# 02-Power.net
KiCad netlist of a schematic drawn in Altium Designer
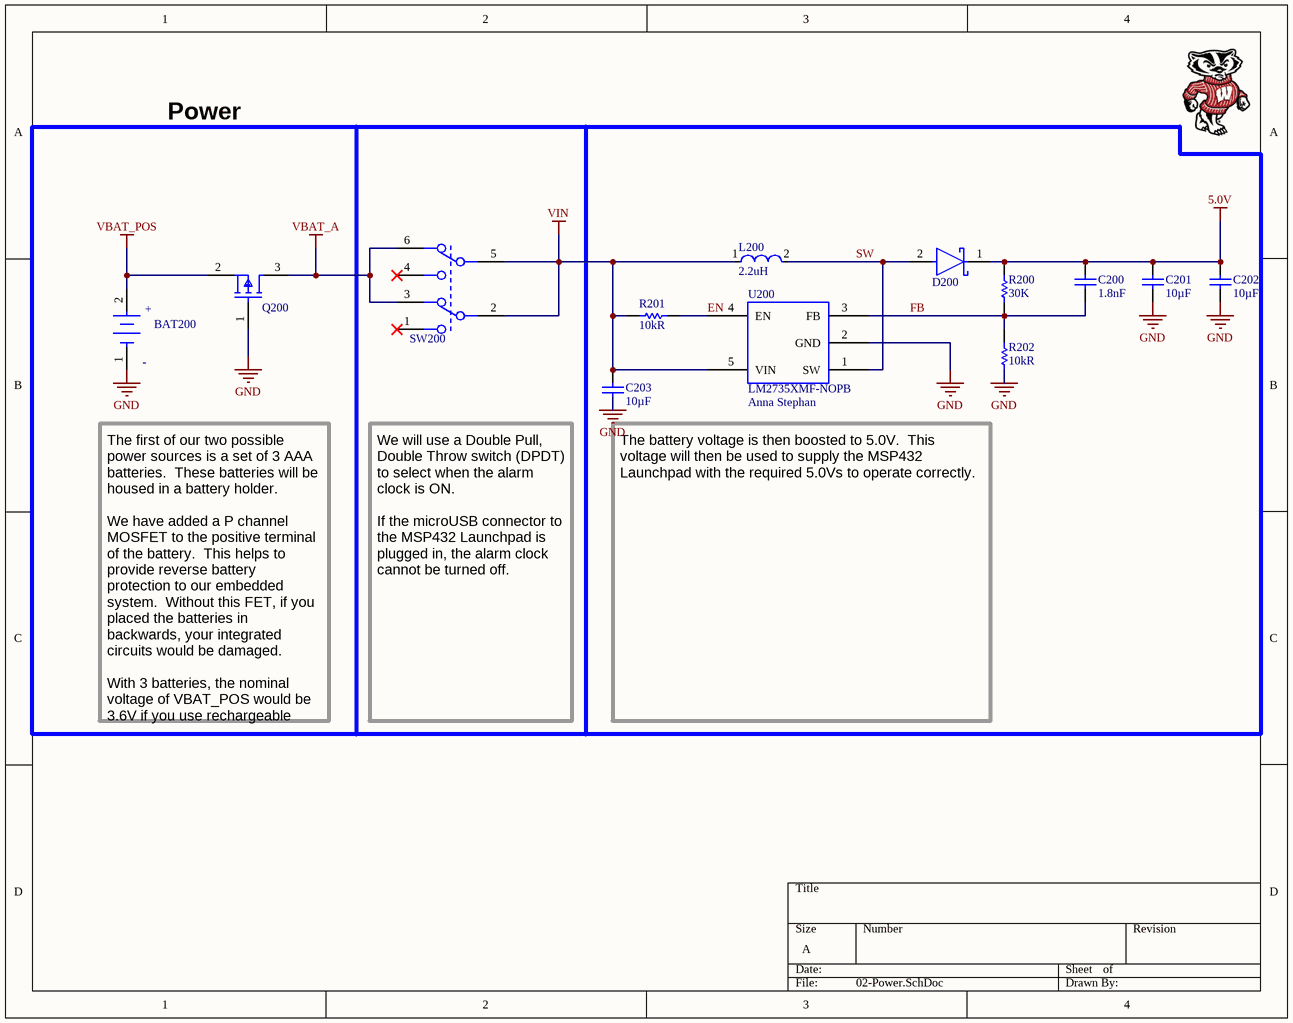
[diagram p0: 02-Power.SchDoc]

(export (version "E")
  (design (tool "Eeschema 10.0.6"))
  (components
    (comp (ref "BAT200")
      (value "UNK_Keystone_2479_eec")
      (footprint "Keystone_2479_0")
      (description "BATTERY HOLDER AAA 3 CELL PC PIN")
      (fields (field (name "PART NUMBER") "2479") (field (name "MANUFACTURER") "Keystone"))
      (libsource (lib "Battery") (part "UNK_Keystone_2479_eec"))
    )
    (comp (ref "C200")
      (value "CAP_0805_N_001_80")
      (footprint "CAP_0805")
      (fields
        (field (name "TOLERANCE") "5%")
        (field (name "VOLTAGE") "50V")
        (field (name "CAPACITANCE") "1.8nF")
      )
      (libsource (lib "ece315") (part "CAP_0805_N_001_80"))
    )
    (comp (ref "C201")
      (value "10µF")
      (footprint "CAP_0805")
      (description "CAP CER 10UF 10V X5R 0805")
      (fields
        (field (name "MANUFACTURER") "Samsung Electro-Mechanics America, Inc.")
        (field (name "MANUFACTURER PART NUMBER") "CL21A106KPCLQNC")
      )
      (libsource (lib "Cap_Ceramic") (part "CAP_0805_U_010_00"))
    )
    (comp (ref "C202")
      (value "10µF")
      (footprint "CAP_0805")
      (description "CAP CER 10UF 10V X5R 0805")
      (fields
        (field (name "MANUFACTURER") "Samsung Electro-Mechanics America, Inc.")
        (field (name "MANUFACTURER PART NUMBER") "CL21A106KPCLQNC")
      )
      (libsource (lib "Cap_Ceramic") (part "CAP_0805_U_010_00"))
    )
    (comp (ref "C203")
      (value "10µF")
      (footprint "CAP_0805")
      (description "CAP CER 10UF 10V X5R 0805")
      (fields
        (field (name "MANUFACTURER") "Samsung Electro-Mechanics America, Inc.")
        (field (name "MANUFACTURER PART NUMBER") "CL21A106KPCLQNC")
      )
      (libsource (lib "Cap_Ceramic") (part "CAP_0805_U_010_00"))
    )
    (comp (ref "D200")
      (value "SM5817PL-TP")
      (footprint "On_Semiconductor_425-04_IPC_A")
      (description "DIODE SCHOTTKY 20V 1A SOD123FL")
      (libsource (lib "ece315") (part "SM5817PL-TP"))
    )
    (comp (ref "L200")
      (value "NRS4018T2R2MDGJ")
      (footprint "IND_TAIYO_NRS4018_TAY")
      (description "Inductor Power Shielded Wirewound 2.2uH 20% 100KHz Ferrite 2.2A 0.0504Ohm DCR 1515 T/R")
      (fields (field (name "TOLERANCE") "20%") (field (name "INDUCTANCE") "2.2uH"))
      (libsource (lib "ece315") (part "NRS4018T2R2MDGJ"))
    )
    (comp (ref "Q200")
      (value "SSM3J328R,LF")
      (footprint "SOT-23_M")
      (description "MOSFET P-CH 20V 6A SOT23F")
      (libsource (lib "Transistors") (part "SSM3J328R,LF"))
    )
    (comp (ref "R200")
      (value "30K")
      (footprint "RES_0805")
      (description "Res Thick Film 0805 30K Ohm 1% 0.125W(1/8W) ±100ppm/°C Pad SMD Automotive T/R")
      (fields (field (name "TOLERANCE") "1%") (field (name "RESISTANCE") "30K"))
      (libsource (lib "ece315") (part "RES_0805_K_030.00"))
    )
    (comp (ref "R201")
      (value "RES_0805_K_010.00")
      (footprint "RES_0805")
      (description "RES SMD 10K OHM 1% 1/8W 0805")
      (fields (field (name "TOLERANCE") "1%") (field (name "RESISTANCE") "10kR"))
      (libsource (lib "ece315") (part "RES_0805_K_010.00"))
    )
    (comp (ref "R202")
      (value "RES_0805_K_010.00")
      (footprint "RES_0805")
      (description "RES SMD 10K OHM 1% 1/8W 0805")
      (fields (field (name "TOLERANCE") "1%") (field (name "RESISTANCE") "10kR"))
      (libsource (lib "ece315") (part "RES_0805_K_010.00"))
    )
    (comp (ref "SW200")
      (value "JS202011SCQN")
      (footprint "C&K_Components_0_MFG")
      (description "C & K COMPONENTS - JS202011SCQN - SWITCH, DPDT, 0.6A, 6VDC, SMD")
      (libsource (lib "Switches") (part "JS202011SCQN"))
    )
    (comp (ref "U200")
      (value "LM2735XMF-NOPB")
      (footprint "LM2735-SOT23-S")
      (description "IC REG MULT CONFG ADJ 2.1A SOT23")
      (fields (field (name "DRAWN_BY") "Anna Stephan"))
      (libsource (lib "ece315") (part "LM2735XMF-NOPB"))
    )
  )
  (nets
    (net (code "1") (name "/EN") (class "Default")
      (node (ref "R201") (pin "1") (pinfunction "1_1") (pintype "passive"))
      (node (ref "U200") (pin "4") (pinfunction "EN_4") (pintype "passive"))
    )
    (net (code "2") (name "/FB") (class "Default")
      (node (ref "C200") (pin "1") (pinfunction "1_1") (pintype "passive"))
      (node (ref "R200") (pin "1") (pinfunction "1_1") (pintype "passive"))
      (node (ref "R202") (pin "2") (pinfunction "2_2") (pintype "passive"))
      (node (ref "U200") (pin "3") (pinfunction "FB_3") (pintype "passive"))
    )
    (net (code "3") (name "/SW") (class "Default")
      (node (ref "D200") (pin "2") (pinfunction "A_2") (pintype "passive"))
      (node (ref "L200") (pin "2") (pinfunction "2_2") (pintype "passive"))
      (node (ref "U200") (pin "1") (pinfunction "SW_1") (pintype "passive"))
    )
    (net (code "4") (name "5.0V") (class "Default")
      (node (ref "C200") (pin "2") (pinfunction "2_2") (pintype "passive"))
      (node (ref "C201") (pin "2") (pinfunction "2_2") (pintype "passive"))
      (node (ref "C202") (pin "2") (pinfunction "2_2") (pintype "passive"))
      (node (ref "D200") (pin "1") (pinfunction "C_1") (pintype "passive"))
      (node (ref "R200") (pin "2") (pinfunction "2_2") (pintype "passive"))
    )
    (net (code "5") (name "GND") (class "Default")
      (node (ref "BAT200") (pin "1") (pinfunction "C_1") (pintype "passive"))
      (node (ref "C201") (pin "1") (pinfunction "1_1") (pintype "passive"))
      (node (ref "C202") (pin "1") (pinfunction "1_1") (pintype "passive"))
      (node (ref "C203") (pin "1") (pinfunction "1_1") (pintype "passive"))
      (node (ref "Q200") (pin "1") (pinfunction "Gate_1") (pintype "passive"))
      (node (ref "R202") (pin "1") (pinfunction "1_1") (pintype "passive"))
      (node (ref "U200") (pin "2") (pinfunction "GND_2") (pintype "passive"))
    )
    (net (code "6") (name "VBAT_A") (class "Default")
      (node (ref "Q200") (pin "3") (pinfunction "Drain_3") (pintype "passive"))
      (node (ref "SW200") (pin "3") (pinfunction "3_3") (pintype "passive"))
      (node (ref "SW200") (pin "6") (pinfunction "6_6") (pintype "passive"))
    )
    (net (code "7") (name "VBAT_POS") (class "Default")
      (node (ref "BAT200") (pin "2") (pinfunction "A_2") (pintype "passive"))
      (node (ref "Q200") (pin "2") (pinfunction "Source_2") (pintype "passive"))
    )
    (net (code "8") (name "VIN") (class "Default")
      (node (ref "C203") (pin "2") (pinfunction "2_2") (pintype "passive"))
      (node (ref "L200") (pin "1") (pinfunction "1_1") (pintype "passive"))
      (node (ref "R201") (pin "2") (pinfunction "2_2") (pintype "passive"))
      (node (ref "SW200") (pin "2") (pinfunction "2_2") (pintype "passive"))
      (node (ref "SW200") (pin "5") (pinfunction "5_5") (pintype "passive"))
      (node (ref "U200") (pin "5") (pinfunction "VIN_5") (pintype "passive"))
    )
    (net (code "9") (name "unconnected-(SW200-Pad1)") (class "Default")
      (node (ref "SW200") (pin "1") (pinfunction "1_1") (pintype "passive+no_connect"))
    )
    (net (code "10") (name "unconnected-(SW200-Pad4)") (class "Default")
      (node (ref "SW200") (pin "4") (pinfunction "4_4") (pintype "passive+no_connect"))
    )
  )
)
